# HomeLight.net
KiCad netlist of a schematic drawn in Altium Designer
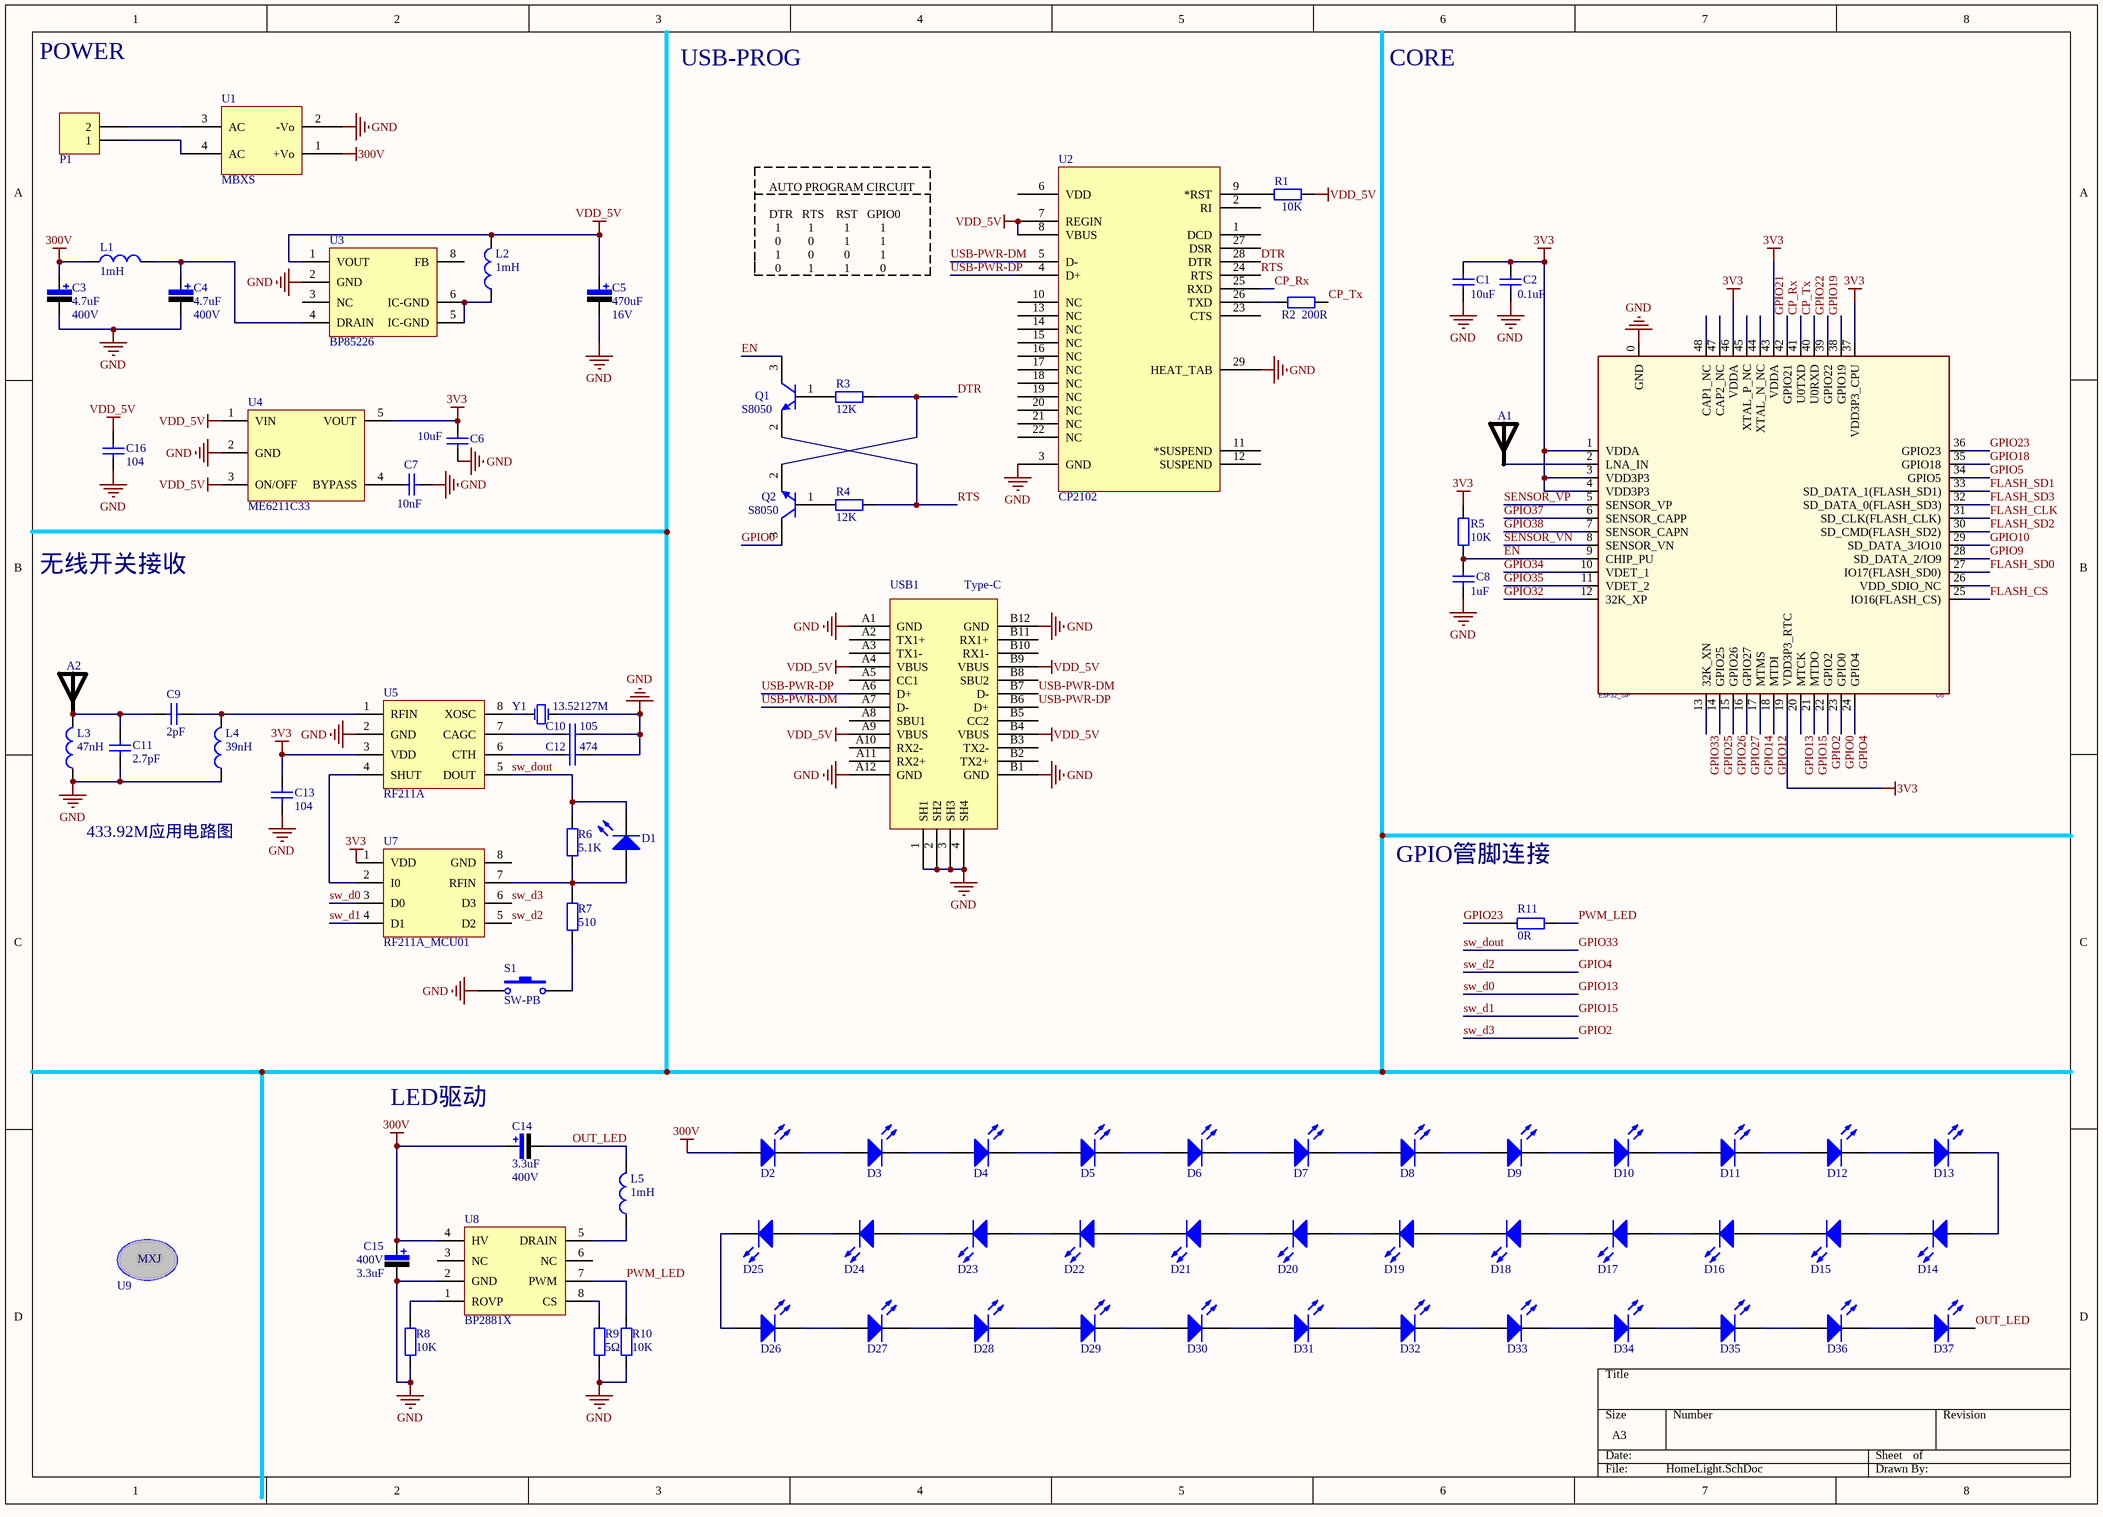
[diagram p0: HomeLight.SchDoc]

(export (version "E")
  (design (tool "Eeschema 10.0.6"))
  (components
    (comp (ref "A1")
      (value "ANT")
      (footprint "ANT5020R2400")
      (libsource (lib "PCBSchlib_SEU_RobotLab") (part "ANT"))
    )
    (comp (ref "A2")
      (value "ANT")
      (footprint "PCBPcblib_SEU_RobotLab:ANT15030R433")
      (libsource (lib "PCBSchlib_SEU_RobotLab") (part "ANT"))
    )
    (comp (ref "C1")
      (value "10uF")
      (footprint "0603-2")
      (description "无极性电容")
      (fields (field (name "PUBLISHER") "Altium Limited"))
      (libsource (lib "PCBSchlib_SEU_RobotLab") (part "Cap"))
    )
    (comp (ref "C2")
      (value "0.1uF")
      (footprint "0603-2")
      (description "无极性电容")
      (fields (field (name "PUBLISHER") "Altium Limited"))
      (libsource (lib "PCBSchlib_SEU_RobotLab") (part "Cap"))
    )
    (comp (ref "C3")
      (value "4.7uF")
      (footprint "SMD-EC-F8")
      (description "极性电解电容")
      (fields
        (field (name "VOL") "400V")
        (field (name "Comment") "Cap Pol")
        (field (name "PUBLISHER") "Altium Limited")
      )
      (libsource (lib "PCBSchlib_SEU_RobotLab") (part "Cap Pol"))
    )
    (comp (ref "C4")
      (value "4.7uF")
      (footprint "SMD-EC-F8")
      (description "极性电解电容")
      (fields
        (field (name "VOL") "400V")
        (field (name "Comment") "Cap Pol")
        (field (name "PUBLISHER") "Altium Limited")
      )
      (libsource (lib "PCBSchlib_SEU_RobotLab") (part "Cap Pol"))
    )
    (comp (ref "C5")
      (value "470uF")
      (footprint "SMD-EC-F6")
      (description "极性电解电容")
      (fields
        (field (name "VOL") "16V")
        (field (name "Comment") "Cap Pol")
        (field (name "PUBLISHER") "Altium Limited")
      )
      (libsource (lib "PCBSchlib_SEU_RobotLab") (part "Cap Pol"))
    )
    (comp (ref "C6")
      (value "10uF")
      (footprint "0603-2")
      (description "无极性电容")
      (fields (field (name "PUBLISHER") "Altium Limited"))
      (libsource (lib "PCBSchlib_SEU_RobotLab") (part "Cap"))
    )
    (comp (ref "C7")
      (value "10nF")
      (footprint "0603-2")
      (description "无极性电容")
      (fields (field (name "PUBLISHER") "Altium Limited"))
      (libsource (lib "PCBSchlib_SEU_RobotLab") (part "Cap"))
    )
    (comp (ref "C8")
      (value "1uF")
      (footprint "0603-2")
      (description "无极性电容")
      (fields (field (name "PUBLISHER") "Altium Limited"))
      (libsource (lib "PCBSchlib_SEU_RobotLab") (part "Cap"))
    )
    (comp (ref "C9")
      (value "2pF")
      (footprint "0603-2")
      (description "无极性电容")
      (fields (field (name "Comment") "Cap") (field (name "PUBLISHER") "Altium Limited"))
      (libsource (lib "PCBSchlib_SEU_RobotLab") (part "Cap"))
    )
    (comp (ref "C10")
      (value "105")
      (footprint "0603-2")
      (description "无极性电容")
      (fields (field (name "Comment") "Cap") (field (name "PUBLISHER") "Altium Limited"))
      (libsource (lib "PCBSchlib_SEU_RobotLab") (part "Cap"))
    )
    (comp (ref "C11")
      (value "2.7pF")
      (footprint "0603-2")
      (description "无极性电容")
      (fields (field (name "Comment") "Cap") (field (name "PUBLISHER") "Altium Limited"))
      (libsource (lib "PCBSchlib_SEU_RobotLab") (part "Cap"))
    )
    (comp (ref "C12")
      (value "474")
      (footprint "0603-2")
      (description "无极性电容")
      (fields (field (name "Comment") "Cap") (field (name "PUBLISHER") "Altium Limited"))
      (libsource (lib "PCBSchlib_SEU_RobotLab") (part "Cap"))
    )
    (comp (ref "C13")
      (value "104")
      (footprint "0603-2")
      (description "无极性电容")
      (fields (field (name "Comment") "Cap") (field (name "PUBLISHER") "Altium Limited"))
      (libsource (lib "PCBSchlib_SEU_RobotLab") (part "Cap"))
    )
    (comp (ref "C14")
      (value "3.3uF")
      (footprint "SMD-EC-F8")
      (description "极性电解电容")
      (fields
        (field (name "VOL") "400V")
        (field (name "Comment") "Cap Pol")
        (field (name "PUBLISHER") "Altium Limited")
      )
      (libsource (lib "") (part "Cap Pol_1"))
    )
    (comp (ref "C15")
      (value "3.3uF")
      (footprint "SMD-EC-F8")
      (description "极性电解电容")
      (fields
        (field (name "VOL") "400V")
        (field (name "Comment") "Cap Pol")
        (field (name "PUBLISHER") "Altium Limited")
      )
      (libsource (lib "PCBSchlib_SEU_RobotLab") (part "Cap Pol"))
    )
    (comp (ref "C16")
      (value "104")
      (footprint "0603-2")
      (description "无极性电容")
      (fields (field (name "Comment") "Cap") (field (name "PUBLISHER") "Altium Limited"))
      (libsource (lib "PCBSchlib_SEU_RobotLab") (part "Cap"))
    )
    (comp (ref "D1")
      (value "LED0")
      (footprint "LED_0603")
      (description "发光二极管")
      (fields (field (name "PUBLISHER") "Altium Limited"))
      (libsource (lib "PCBSchlib_SEU_RobotLab") (part "LED0"))
    )
    (comp (ref "D2")
      (value "LED0")
      (footprint "LED-3528")
      (description "发光二极管")
      (fields (field (name "PUBLISHER") "Altium Limited"))
      (libsource (lib "PCBSchlib_SEU_RobotLab") (part "LED0"))
    )
    (comp (ref "D3")
      (value "LED0")
      (footprint "LED-3528")
      (description "发光二极管")
      (fields (field (name "PUBLISHER") "Altium Limited"))
      (libsource (lib "PCBSchlib_SEU_RobotLab") (part "LED0"))
    )
    (comp (ref "D4")
      (value "LED0")
      (footprint "LED-3528")
      (description "发光二极管")
      (fields (field (name "PUBLISHER") "Altium Limited"))
      (libsource (lib "PCBSchlib_SEU_RobotLab") (part "LED0"))
    )
    (comp (ref "D5")
      (value "LED0")
      (footprint "LED-3528")
      (description "发光二极管")
      (fields (field (name "PUBLISHER") "Altium Limited"))
      (libsource (lib "PCBSchlib_SEU_RobotLab") (part "LED0"))
    )
    (comp (ref "D6")
      (value "LED0")
      (footprint "LED-3528")
      (description "发光二极管")
      (fields (field (name "PUBLISHER") "Altium Limited"))
      (libsource (lib "PCBSchlib_SEU_RobotLab") (part "LED0"))
    )
    (comp (ref "D7")
      (value "LED0")
      (footprint "LED-3528")
      (description "发光二极管")
      (fields (field (name "PUBLISHER") "Altium Limited"))
      (libsource (lib "PCBSchlib_SEU_RobotLab") (part "LED0"))
    )
    (comp (ref "D8")
      (value "LED0")
      (footprint "LED-3528")
      (description "发光二极管")
      (fields (field (name "PUBLISHER") "Altium Limited"))
      (libsource (lib "PCBSchlib_SEU_RobotLab") (part "LED0"))
    )
    (comp (ref "D9")
      (value "LED0")
      (footprint "LED-3528")
      (description "发光二极管")
      (fields (field (name "PUBLISHER") "Altium Limited"))
      (libsource (lib "PCBSchlib_SEU_RobotLab") (part "LED0"))
    )
    (comp (ref "D10")
      (value "LED0")
      (footprint "LED-3528")
      (description "发光二极管")
      (fields (field (name "PUBLISHER") "Altium Limited"))
      (libsource (lib "PCBSchlib_SEU_RobotLab") (part "LED0"))
    )
    (comp (ref "D11")
      (value "LED0")
      (footprint "LED-3528")
      (description "发光二极管")
      (fields (field (name "PUBLISHER") "Altium Limited"))
      (libsource (lib "PCBSchlib_SEU_RobotLab") (part "LED0"))
    )
    (comp (ref "D12")
      (value "LED0")
      (footprint "LED-3528")
      (description "发光二极管")
      (fields (field (name "PUBLISHER") "Altium Limited"))
      (libsource (lib "PCBSchlib_SEU_RobotLab") (part "LED0"))
    )
    (comp (ref "D13")
      (value "LED0")
      (footprint "LED-3528")
      (description "发光二极管")
      (fields (field (name "PUBLISHER") "Altium Limited"))
      (libsource (lib "PCBSchlib_SEU_RobotLab") (part "LED0"))
    )
    (comp (ref "D14")
      (value "LED0")
      (footprint "LED-3528")
      (description "发光二极管")
      (fields (field (name "PUBLISHER") "Altium Limited"))
      (libsource (lib "PCBSchlib_SEU_RobotLab") (part "LED0"))
    )
    (comp (ref "D15")
      (value "LED0")
      (footprint "LED-3528")
      (description "发光二极管")
      (fields (field (name "PUBLISHER") "Altium Limited"))
      (libsource (lib "PCBSchlib_SEU_RobotLab") (part "LED0"))
    )
    (comp (ref "D16")
      (value "LED0")
      (footprint "LED-3528")
      (description "发光二极管")
      (fields (field (name "PUBLISHER") "Altium Limited"))
      (libsource (lib "PCBSchlib_SEU_RobotLab") (part "LED0"))
    )
    (comp (ref "D17")
      (value "LED0")
      (footprint "LED-3528")
      (description "发光二极管")
      (fields (field (name "PUBLISHER") "Altium Limited"))
      (libsource (lib "PCBSchlib_SEU_RobotLab") (part "LED0"))
    )
    (comp (ref "D18")
      (value "LED0")
      (footprint "LED-3528")
      (description "发光二极管")
      (fields (field (name "PUBLISHER") "Altium Limited"))
      (libsource (lib "PCBSchlib_SEU_RobotLab") (part "LED0"))
    )
    (comp (ref "D19")
      (value "LED0")
      (footprint "LED-3528")
      (description "发光二极管")
      (fields (field (name "PUBLISHER") "Altium Limited"))
      (libsource (lib "PCBSchlib_SEU_RobotLab") (part "LED0"))
    )
    (comp (ref "D20")
      (value "LED0")
      (footprint "LED-3528")
      (description "发光二极管")
      (fields (field (name "PUBLISHER") "Altium Limited"))
      (libsource (lib "PCBSchlib_SEU_RobotLab") (part "LED0"))
    )
    (comp (ref "D21")
      (value "LED0")
      (footprint "LED-3528")
      (description "发光二极管")
      (fields (field (name "PUBLISHER") "Altium Limited"))
      (libsource (lib "PCBSchlib_SEU_RobotLab") (part "LED0"))
    )
    (comp (ref "D22")
      (value "LED0")
      (footprint "LED-3528")
      (description "发光二极管")
      (fields (field (name "PUBLISHER") "Altium Limited"))
      (libsource (lib "PCBSchlib_SEU_RobotLab") (part "LED0"))
    )
    (comp (ref "D23")
      (value "LED0")
      (footprint "LED-3528")
      (description "发光二极管")
      (fields (field (name "PUBLISHER") "Altium Limited"))
      (libsource (lib "PCBSchlib_SEU_RobotLab") (part "LED0"))
    )
    (comp (ref "D24")
      (value "LED0")
      (footprint "LED-3528")
      (description "发光二极管")
      (fields (field (name "PUBLISHER") "Altium Limited"))
      (libsource (lib "PCBSchlib_SEU_RobotLab") (part "LED0"))
    )
    (comp (ref "D25")
      (value "LED0")
      (footprint "LED-3528")
      (description "发光二极管")
      (fields (field (name "PUBLISHER") "Altium Limited"))
      (libsource (lib "PCBSchlib_SEU_RobotLab") (part "LED0"))
    )
    (comp (ref "D26")
      (value "LED0")
      (footprint "LED-3528")
      (description "发光二极管")
      (fields (field (name "PUBLISHER") "Altium Limited"))
      (libsource (lib "PCBSchlib_SEU_RobotLab") (part "LED0"))
    )
    (comp (ref "D27")
      (value "LED0")
      (footprint "LED-3528")
      (description "发光二极管")
      (fields (field (name "PUBLISHER") "Altium Limited"))
      (libsource (lib "PCBSchlib_SEU_RobotLab") (part "LED0"))
    )
    (comp (ref "D28")
      (value "LED0")
      (footprint "LED-3528")
      (description "发光二极管")
      (fields (field (name "PUBLISHER") "Altium Limited"))
      (libsource (lib "PCBSchlib_SEU_RobotLab") (part "LED0"))
    )
    (comp (ref "D29")
      (value "LED0")
      (footprint "LED-3528")
      (description "发光二极管")
      (fields (field (name "PUBLISHER") "Altium Limited"))
      (libsource (lib "PCBSchlib_SEU_RobotLab") (part "LED0"))
    )
    (comp (ref "D30")
      (value "LED0")
      (footprint "LED-3528")
      (description "发光二极管")
      (fields (field (name "PUBLISHER") "Altium Limited"))
      (libsource (lib "PCBSchlib_SEU_RobotLab") (part "LED0"))
    )
    (comp (ref "D31")
      (value "LED0")
      (footprint "LED-3528")
      (description "发光二极管")
      (fields (field (name "PUBLISHER") "Altium Limited"))
      (libsource (lib "PCBSchlib_SEU_RobotLab") (part "LED0"))
    )
    (comp (ref "D32")
      (value "LED0")
      (footprint "LED-3528")
      (description "发光二极管")
      (fields (field (name "PUBLISHER") "Altium Limited"))
      (libsource (lib "PCBSchlib_SEU_RobotLab") (part "LED0"))
    )
    (comp (ref "D33")
      (value "LED0")
      (footprint "LED-3528")
      (description "发光二极管")
      (fields (field (name "PUBLISHER") "Altium Limited"))
      (libsource (lib "PCBSchlib_SEU_RobotLab") (part "LED0"))
    )
    (comp (ref "D34")
      (value "LED0")
      (footprint "LED-3528")
      (description "发光二极管")
      (fields (field (name "PUBLISHER") "Altium Limited"))
      (libsource (lib "PCBSchlib_SEU_RobotLab") (part "LED0"))
    )
    (comp (ref "D35")
      (value "LED0")
      (footprint "LED-3528")
      (description "发光二极管")
      (fields (field (name "PUBLISHER") "Altium Limited"))
      (libsource (lib "PCBSchlib_SEU_RobotLab") (part "LED0"))
    )
    (comp (ref "D36")
      (value "LED0")
      (footprint "LED-3528")
      (description "发光二极管")
      (fields (field (name "PUBLISHER") "Altium Limited"))
      (libsource (lib "PCBSchlib_SEU_RobotLab") (part "LED0"))
    )
    (comp (ref "D37")
      (value "LED0")
      (footprint "LED-3528")
      (description "发光二极管")
      (fields (field (name "PUBLISHER") "Altium Limited"))
      (libsource (lib "PCBSchlib_SEU_RobotLab") (part "LED0"))
    )
    (comp (ref "L1")
      (value "1mH")
      (footprint "L12x12")
      (description "电感")
      (fields (field (name "Comment") "Inductor") (field (name "PUBLISHER") "Altium Limited"))
      (libsource (lib "PCBSchlib_SEU_RobotLab") (part "Inductor"))
    )
    (comp (ref "L2")
      (value "1mH")
      (footprint "L12x12")
      (description "电感")
      (fields (field (name "Comment") "Inductor") (field (name "PUBLISHER") "Altium Limited"))
      (libsource (lib "PCBSchlib_SEU_RobotLab") (part "Inductor"))
    )
    (comp (ref "L3")
      (value "47nH")
      (footprint "PCBPcblib_SEU_RobotLab:0603-1")
      (description "电感")
      (fields (field (name "Comment") "Inductor") (field (name "PUBLISHER") "Altium Limited"))
      (libsource (lib "PCBSchlib_SEU_RobotLab") (part "Inductor"))
    )
    (comp (ref "L4")
      (value "39nH")
      (footprint "PCBPcblib_SEU_RobotLab:0603-1")
      (description "电感")
      (fields (field (name "Comment") "Inductor") (field (name "PUBLISHER") "Altium Limited"))
      (libsource (lib "PCBSchlib_SEU_RobotLab") (part "Inductor"))
    )
    (comp (ref "L5")
      (value "1mH")
      (footprint "L12x12")
      (description "电感")
      (fields (field (name "Comment") "Inductor") (field (name "PUBLISHER") "Altium Limited"))
      (libsource (lib "PCBSchlib_SEU_RobotLab") (part "Inductor"))
    )
    (comp (ref "P1")
      (value "Header 2")
      (footprint "PCBPcblib_SEU_RobotLab:HDR2X1_焊接版")
      (description "接插件")
      (fields (field (name "PUBLISHER") "Altium Limited"))
      (libsource (lib "PCBSchlib_SEU_RobotLab") (part "Header 2"))
    )
    (comp (ref "Q1")
      (value "S8050")
      (footprint "PCBPcblib_SEU_RobotLab:SOT-23")
      (description "NPN三极管")
      (fields (field (name "PUBLISHER") "Altium Limited"))
      (libsource (lib "PCBSchlib_SEU_RobotLab") (part "Triode-NPN"))
    )
    (comp (ref "Q2")
      (value "S8050")
      (footprint "PCBPcblib_SEU_RobotLab:SOT-23")
      (description "NPN三极管")
      (fields (field (name "PUBLISHER") "Altium Limited"))
      (libsource (lib "PCBSchlib_SEU_RobotLab") (part "Triode-NPN"))
    )
    (comp (ref "R1")
      (value "10K")
      (footprint "0603-1")
      (description "贴片电阻")
      (fields (field (name "PUBLISHER") "Altium Limited"))
      (libsource (lib "PCBSchlib_SEU_RobotLab") (part "Res1"))
    )
    (comp (ref "R2")
      (value "200R")
      (footprint "0603-1")
      (description "贴片电阻")
      (fields (field (name "PUBLISHER") "Altium Limited"))
      (libsource (lib "PCBSchlib_SEU_RobotLab") (part "Res1"))
    )
    (comp (ref "R3")
      (value "12K")
      (footprint "0603-1")
      (description "贴片电阻")
      (fields (field (name "PUBLISHER") "Altium Limited"))
      (libsource (lib "PCBSchlib_SEU_RobotLab") (part "Res1"))
    )
    (comp (ref "R4")
      (value "12K")
      (footprint "0603-1")
      (description "贴片电阻")
      (fields (field (name "PUBLISHER") "Altium Limited"))
      (libsource (lib "PCBSchlib_SEU_RobotLab") (part "Res1"))
    )
    (comp (ref "R5")
      (value "10K")
      (footprint "0603-1")
      (description "贴片电阻")
      (fields (field (name "PUBLISHER") "Altium Limited"))
      (libsource (lib "") (part "Res1_2"))
    )
    (comp (ref "R6")
      (value "5.1K")
      (footprint "0603-1")
      (description "贴片电阻")
      (fields (field (name "Comment") "Res1") (field (name "PUBLISHER") "Altium Limited"))
      (libsource (lib "") (part "Res1_1"))
    )
    (comp (ref "R7")
      (value "510")
      (footprint "0603-1")
      (description "贴片电阻")
      (fields (field (name "Comment") "Res1") (field (name "PUBLISHER") "Altium Limited"))
      (libsource (lib "") (part "Res1_1"))
    )
    (comp (ref "R8")
      (value "10K")
      (footprint "0603-1")
      (description "贴片电阻")
      (fields (field (name "Comment") "Res1") (field (name "PUBLISHER") "Altium Limited"))
      (libsource (lib "") (part "Res1_1"))
    )
    (comp (ref "R9")
      (value "5Ω")
      (footprint "0603-1")
      (description "贴片电阻")
      (fields (field (name "Comment") "Res1") (field (name "PUBLISHER") "Altium Limited"))
      (libsource (lib "") (part "Res1_1"))
    )
    (comp (ref "R10")
      (value "10K")
      (footprint "0603-1")
      (description "贴片电阻")
      (fields (field (name "Comment") "Res1") (field (name "PUBLISHER") "Altium Limited"))
      (libsource (lib "") (part "Res1_1"))
    )
    (comp (ref "R11")
      (value "0R")
      (footprint "0603-1")
      (description "贴片电阻")
      (fields (field (name "Comment") "Res1") (field (name "PUBLISHER") "Altium Limited"))
      (libsource (lib "PCBSchlib_SEU_RobotLab") (part "Res1"))
    )
    (comp (ref "S1")
      (value "SW-PB")
      (footprint "SW_PB2_A1")
      (description "微动开关")
      (fields (field (name "PUBLISHER") "Altium Limited"))
      (libsource (lib "PCBSchlib_SEU_RobotLab") (part "SW-PB"))
    )
    (comp (ref "U1")
      (value "MBXS")
      (footprint "PCBPcblib_SEU_RobotLab:MBXS")
      (description "整流桥")
      (libsource (lib "PCBSchlib_SEU_RobotLab") (part "MBXS"))
    )
    (comp (ref "U2")
      (value "CP2102")
      (footprint "QFN-28")
      (description "USB转TTL")
      (libsource (lib "mLib") (part "CP2102"))
    )
    (comp (ref "U3")
      (value "BP85226")
      (footprint "PCBPcblib_SEU_RobotLab:BP85226-BP2881")
      (description "开关电源驱动芯片")
      (libsource (lib "PCBSchlib_SEU_RobotLab") (part "BP85226"))
    )
    (comp (ref "U4")
      (value "ME6211C33")
      (footprint "SOT23-5")
      (description "LDO")
      (libsource (lib "PCBSchlib_SEU_RobotLab") (part "LP2992"))
    )
    (comp (ref "U5")
      (value "RF211A")
      (footprint "PCBPcblib_SEU_RobotLab:SOIC-8")
      (description "315M无线接收芯片")
      (libsource (lib "PCBSchlib_SEU_RobotLab") (part "RF211A"))
    )
    (comp (ref "U6")
      (value "ESP32_SIP")
      (footprint "QFN-48_7X7")
      (libsource (lib "PCBSchlib_SEU_RobotLab") (part "ESP32-PICO"))
    )
    (comp (ref "U7")
      (value "RF211A_MCU01")
      (footprint "PCBPcblib_SEU_RobotLab:SOIC-8")
      (description "无线接收芯片的解码芯片")
      (libsource (lib "PCBSchlib_SEU_RobotLab") (part "RF211A_MCU01"))
    )
    (comp (ref "U8")
      (value "BP2881X")
      (footprint "PCBPcblib_SEU_RobotLab:BP85226-BP2881")
      (description "PWM调光非隔离降压型LED恒流驱动芯片")
      (libsource (lib "PCBSchlib_SEU_RobotLab") (part "BP2881X"))
    )
    (comp (ref "U9")
      (value "logo_MXJ")
      (footprint "PCBPcblib_SEU_RobotLab:logo_MXJ")
      (libsource (lib "PCBSchlib_SEU_RobotLab") (part "logo_MXJ"))
    )
    (comp (ref "USB1")
      (value "Type-C")
      (footprint "Type-C-TOP")
      (libsource (lib "PCBSchlib_SEU_RobotLab") (part "USB-Type-C-TOP"))
    )
    (comp (ref "Y1")
      (value "13.52127M")
      (footprint "X-SM49")
      (description "晶振")
      (fields (field (name "Comment") "XTAL") (field (name "PUBLISHER") "Altium Limited"))
      (libsource (lib "PCBSchlib_SEU_RobotLab") (part "XTAL"))
    )
  )
  (nets
    (net (code "1") (name "/CP_Rx") (class "Default")
      (node (ref "U2") (pin "25") (pinfunction "RXD_25") (pintype "passive"))
      (node (ref "U6") (pin "41") (pinfunction "U0TXD_41") (pintype "power_in"))
    )
    (net (code "2") (name "/CP_Tx") (class "Default")
      (node (ref "R2") (pin "1") (pinfunction "1_1") (pintype "passive"))
      (node (ref "U6") (pin "40") (pinfunction "U0RXD_40") (pintype "power_in"))
    )
    (net (code "3") (name "/DTR") (class "Default")
      (node (ref "Q2") (pin "2") (pinfunction "E_2") (pintype "passive"))
      (node (ref "R3") (pin "1") (pinfunction "1_1") (pintype "passive"))
      (node (ref "U2") (pin "28") (pinfunction "DTR_28") (pintype "passive"))
    )
    (net (code "4") (name "/EN") (class "Default")
      (node (ref "C8") (pin "1") (pinfunction "1_1") (pintype "passive"))
      (node (ref "Q1") (pin "3") (pinfunction "C_3") (pintype "passive"))
      (node (ref "R5") (pin "2") (pinfunction "2_2") (pintype "passive"))
      (node (ref "U6") (pin "9") (pinfunction "CHIP_PU_9") (pintype "passive"))
    )
    (net (code "5") (name "/FLASH_CLK") (class "Default")
      (node (ref "U6") (pin "31") (pinfunction "SD_CLK(FLASH_CLK)_31") (pintype "passive"))
    )
    (net (code "6") (name "/FLASH_CS") (class "Default")
      (node (ref "U6") (pin "25") (pinfunction "IO16(FLASH_CS)_25") (pintype "passive"))
    )
    (net (code "7") (name "/FLASH_SD0") (class "Default")
      (node (ref "U6") (pin "27") (pinfunction "IO17(FLASH_SD0)_27") (pintype "passive"))
    )
    (net (code "8") (name "/FLASH_SD1") (class "Default")
      (node (ref "U6") (pin "33") (pinfunction "SD_DATA_1(FLASH_SD1)_33") (pintype "passive"))
    )
    (net (code "9") (name "/FLASH_SD2") (class "Default")
      (node (ref "U6") (pin "30") (pinfunction "SD_CMD(FLASH_SD2)_30") (pintype "passive"))
    )
    (net (code "10") (name "/FLASH_SD3") (class "Default")
      (node (ref "U6") (pin "32") (pinfunction "SD_DATA_0(FLASH_SD3)_32") (pintype "passive"))
    )
    (net (code "11") (name "/GPIO0") (class "Default")
      (node (ref "Q2") (pin "3") (pinfunction "C_3") (pintype "passive"))
      (node (ref "U6") (pin "23") (pinfunction "GPIO0_23") (pintype "passive"))
    )
    (net (code "12") (name "/GPIO2") (class "Default")
      (node (ref "U6") (pin "22") (pinfunction "GPIO2_22") (pintype "passive"))
      (node (ref "U7") (pin "6") (pinfunction "D3_6") (pintype "passive"))
    )
    (net (code "13") (name "/GPIO4") (class "Default")
      (node (ref "U6") (pin "24") (pinfunction "GPIO4_24") (pintype "passive"))
      (node (ref "U7") (pin "5") (pinfunction "D2_5") (pintype "passive"))
    )
    (net (code "14") (name "/GPIO5") (class "Default")
      (node (ref "U6") (pin "34") (pinfunction "GPIO5_34") (pintype "passive"))
    )
    (net (code "15") (name "/GPIO9") (class "Default")
      (node (ref "U6") (pin "28") (pinfunction "SD_DATA_2/IO9_28") (pintype "passive"))
    )
    (net (code "16") (name "/GPIO10") (class "Default")
      (node (ref "U6") (pin "29") (pinfunction "SD_DATA_3/IO10_29") (pintype "passive"))
    )
    (net (code "17") (name "/GPIO12") (class "Default")
      (node (ref "U6") (pin "18") (pinfunction "MTDI_18") (pintype "passive"))
    )
    (net (code "18") (name "/GPIO13") (class "Default")
      (node (ref "U6") (pin "20") (pinfunction "MTCK_20") (pintype "passive"))
      (node (ref "U7") (pin "3") (pinfunction "D0_3") (pintype "passive"))
    )
    (net (code "19") (name "/GPIO14") (class "Default")
      (node (ref "U6") (pin "17") (pinfunction "MTMS_17") (pintype "passive"))
    )
    (net (code "20") (name "/GPIO15") (class "Default")
      (node (ref "U6") (pin "21") (pinfunction "MTDO_21") (pintype "passive"))
      (node (ref "U7") (pin "4") (pinfunction "D1_4") (pintype "passive"))
    )
    (net (code "21") (name "/GPIO18") (class "Default")
      (node (ref "U6") (pin "35") (pinfunction "GPIO18_35") (pintype "passive"))
    )
    (net (code "22") (name "/GPIO19") (class "Default")
      (node (ref "U6") (pin "38") (pinfunction "GPIO19_38") (pintype "passive"))
    )
    (net (code "23") (name "/GPIO21") (class "Default")
      (node (ref "U6") (pin "42") (pinfunction "GPIO21_42") (pintype "passive"))
    )
    (net (code "24") (name "/GPIO22") (class "Default")
      (node (ref "U6") (pin "39") (pinfunction "GPIO22_39") (pintype "passive"))
    )
    (net (code "25") (name "/GPIO23") (class "Default")
      (node (ref "R11") (pin "2") (pinfunction "2_2") (pintype "passive"))
      (node (ref "U6") (pin "36") (pinfunction "GPIO23_36") (pintype "passive"))
    )
    (net (code "26") (name "/GPIO25") (class "Default")
      (node (ref "U6") (pin "14") (pinfunction "GPIO25_14") (pintype "passive"))
    )
    (net (code "27") (name "/GPIO26") (class "Default")
      (node (ref "U6") (pin "15") (pinfunction "GPIO26_15") (pintype "passive"))
    )
    (net (code "28") (name "/GPIO27") (class "Default")
      (node (ref "U6") (pin "16") (pinfunction "GPIO27_16") (pintype "passive"))
    )
    (net (code "29") (name "/GPIO32") (class "Default")
      (node (ref "U6") (pin "12") (pinfunction "32K_XP_12") (pintype "passive"))
    )
    (net (code "30") (name "/GPIO33") (class "Default")
      (node (ref "D1") (pin "2") (pinfunction "K_2") (pintype "passive"))
      (node (ref "R6") (pin "2") (pinfunction "2_2") (pintype "passive"))
      (node (ref "U5") (pin "5") (pinfunction "DOUT_5") (pintype "passive"))
      (node (ref "U6") (pin "13") (pinfunction "32K_XN_13") (pintype "passive"))
    )
    (net (code "31") (name "/GPIO34") (class "Default")
      (node (ref "U6") (pin "10") (pinfunction "VDET_1_10") (pintype "passive"))
    )
    (net (code "32") (name "/GPIO35") (class "Default")
      (node (ref "U6") (pin "11") (pinfunction "VDET_2_11") (pintype "passive"))
    )
    (net (code "33") (name "/GPIO37") (class "Default")
      (node (ref "U6") (pin "6") (pinfunction "SENSOR_CAPP_6") (pintype "passive"))
    )
    (net (code "34") (name "/GPIO38") (class "Default")
      (node (ref "U6") (pin "7") (pinfunction "SENSOR_CAPN_7") (pintype "passive"))
    )
    (net (code "35") (name "/OUT_LED") (class "Default")
      (node (ref "C14") (pin "2") (pinfunction "2_2") (pintype "passive"))
      (node (ref "D37") (pin "2") (pinfunction "K_2") (pintype "passive"))
      (node (ref "L5") (pin "2") (pinfunction "2_2") (pintype "passive"))
    )
    (net (code "36") (name "/PWM_LED") (class "Default")
      (node (ref "R10") (pin "2") (pinfunction "2_2") (pintype "passive"))
      (node (ref "R11") (pin "1") (pinfunction "1_1") (pintype "passive"))
      (node (ref "U8") (pin "7") (pinfunction "PWM_7") (pintype "passive"))
    )
    (net (code "37") (name "/RTS") (class "Default")
      (node (ref "Q1") (pin "2") (pinfunction "E_2") (pintype "passive"))
      (node (ref "R4") (pin "1") (pinfunction "1_1") (pintype "passive"))
      (node (ref "U2") (pin "24") (pinfunction "RTS_24") (pintype "passive"))
    )
    (net (code "38") (name "/SENSOR_VN") (class "Default")
      (node (ref "U6") (pin "8") (pinfunction "SENSOR_VN_8") (pintype "passive"))
    )
    (net (code "39") (name "/SENSOR_VP") (class "Default")
      (node (ref "U6") (pin "5") (pinfunction "SENSOR_VP_5") (pintype "passive"))
    )
    (net (code "40") (name "/USB-PWR-DM") (class "Default")
      (node (ref "U2") (pin "5") (pinfunction "D-_5") (pintype "passive"))
      (node (ref "USB1") (pin "A7") (pinfunction "D-_A7") (pintype "passive"))
      (node (ref "USB1") (pin "B7") (pinfunction "D-_B7") (pintype "passive"))
    )
    (net (code "41") (name "/USB-PWR-DP") (class "Default")
      (node (ref "U2") (pin "4") (pinfunction "D+_4") (pintype "passive"))
      (node (ref "USB1") (pin "A6") (pinfunction "D+_A6") (pintype "passive"))
      (node (ref "USB1") (pin "B6") (pinfunction "D+_B6") (pintype "passive"))
    )
    (net (code "42") (name "3V3") (class "Default")
      (node (ref "C1") (pin "2") (pinfunction "2_2") (pintype "passive"))
      (node (ref "C13") (pin "1") (pinfunction "1_1") (pintype "passive"))
      (node (ref "C2") (pin "2") (pinfunction "2_2") (pintype "passive"))
      (node (ref "C6") (pin "2") (pinfunction "2_2") (pintype "passive"))
      (node (ref "R5") (pin "1") (pinfunction "1_1") (pintype "passive"))
      (node (ref "U4") (pin "5") (pinfunction "VOUT_5") (pintype "passive"))
      (node (ref "U5") (pin "3") (pinfunction "VDD_3") (pintype "passive"))
      (node (ref "U6") (pin "1") (pinfunction "VDDA_1") (pintype "power_in"))
      (node (ref "U6") (pin "19") (pinfunction "VDD3P3_RTC_19") (pintype "power_in"))
      (node (ref "U6") (pin "3") (pinfunction "VDD3P3_3") (pintype "power_in"))
      (node (ref "U6") (pin "37") (pinfunction "VDD3P3_CPU_37") (pintype "power_in"))
      (node (ref "U6") (pin "4") (pinfunction "VDD3P3_4") (pintype "power_in"))
      (node (ref "U6") (pin "43") (pinfunction "VDDA_43") (pintype "power_in"))
      (node (ref "U6") (pin "46") (pinfunction "VDDA_46") (pintype "power_in"))
      (node (ref "U7") (pin "1") (pinfunction "VDD_1") (pintype "passive"))
    )
    (net (code "43") (name "300V") (class "Default")
      (node (ref "C14") (pin "1") (pinfunction "1_1") (pintype "passive"))
      (node (ref "C15") (pin "1") (pinfunction "1_1") (pintype "passive"))
      (node (ref "C3") (pin "1") (pinfunction "1_1") (pintype "passive"))
      (node (ref "D2") (pin "1") (pinfunction "A_1") (pintype "passive"))
      (node (ref "L1") (pin "1") (pinfunction "1_1") (pintype "passive"))
      (node (ref "U1") (pin "1") (pinfunction "+Vo_1") (pintype "passive"))
      (node (ref "U8") (pin "4") (pinfunction "HV_4") (pintype "passive"))
    )
    (net (code "44") (name "GND") (class "Default")
      (node (ref "C1") (pin "1") (pinfunction "1_1") (pintype "passive"))
      (node (ref "C10") (pin "1") (pinfunction "1_1") (pintype "passive"))
      (node (ref "C11") (pin "2") (pinfunction "2_2") (pintype "passive"))
      (node (ref "C12") (pin "1") (pinfunction "1_1") (pintype "passive"))
      (node (ref "C13") (pin "2") (pinfunction "2_2") (pintype "passive"))
      (node (ref "C15") (pin "2") (pinfunction "2_2") (pintype "passive"))
      (node (ref "C16") (pin "2") (pinfunction "2_2") (pintype "passive"))
      (node (ref "C2") (pin "1") (pinfunction "1_1") (pintype "passive"))
      (node (ref "C3") (pin "2") (pinfunction "2_2") (pintype "passive"))
      (node (ref "C4") (pin "2") (pinfunction "2_2") (pintype "passive"))
      (node (ref "C5") (pin "2") (pinfunction "2_2") (pintype "passive"))
      (node (ref "C6") (pin "1") (pinfunction "1_1") (pintype "passive"))
      (node (ref "C7") (pin "1") (pinfunction "1_1") (pintype "passive"))
      (node (ref "C8") (pin "2") (pinfunction "2_2") (pintype "passive"))
      (node (ref "L3") (pin "1") (pinfunction "1_1") (pintype "passive"))
      (node (ref "L4") (pin "1") (pinfunction "1_1") (pintype "passive"))
      (node (ref "R10") (pin "1") (pinfunction "1_1") (pintype "passive"))
      (node (ref "R8") (pin "1") (pinfunction "1_1") (pintype "passive"))
      (node (ref "R9") (pin "1") (pinfunction "1_1") (pintype "passive"))
      (node (ref "S1") (pin "1") (pinfunction "1_1") (pintype "passive"))
      (node (ref "U1") (pin "2") (pinfunction "-Vo_2") (pintype "passive"))
      (node (ref "U2") (pin "29") (pinfunction "HEAT_TAB_29") (pintype "passive"))
      (node (ref "U2") (pin "3") (pinfunction "GND_3") (pintype "passive"))
      (node (ref "U3") (pin "2") (pinfunction "GND_2") (pintype "passive"))
      (node (ref "U4") (pin "2") (pinfunction "GND_2") (pintype "passive"))
      (node (ref "U5") (pin "2") (pinfunction "GND_2") (pintype "passive"))
      (node (ref "U6") (pin "0") (pinfunction "GND_0") (pintype "power_in"))
      (node (ref "U8") (pin "2") (pinfunction "GND_2") (pintype "passive"))
      (node (ref "USB1") (pin "1") (pinfunction "SH1_1") (pintype "passive"))
      (node (ref "USB1") (pin "2") (pinfunction "SH2_2") (pintype "passive"))
      (node (ref "USB1") (pin "3") (pinfunction "SH3_3") (pintype "passive"))
      (node (ref "USB1") (pin "4") (pinfunction "SH4_4") (pintype "passive"))
      (node (ref "USB1") (pin "A1") (pinfunction "GND_A1") (pintype "passive"))
      (node (ref "USB1") (pin "A12") (pinfunction "GND_A12") (pintype "passive"))
      (node (ref "USB1") (pin "B1") (pinfunction "GND_B1") (pintype "passive"))
      (node (ref "USB1") (pin "B12") (pinfunction "GND_B12") (pintype "passive"))
      (node (ref "Y1") (pin "2") (pinfunction "2_2") (pintype "passive"))
    )
    (net (code "45") (name "Net-(A2-Pad1)") (class "Default")
      (node (ref "A2") (pin "1") (pinfunction "1_1") (pintype "passive"))
      (node (ref "C11") (pin "1") (pinfunction "1_1") (pintype "passive"))
      (node (ref "C9") (pin "1") (pinfunction "1_1") (pintype "passive"))
      (node (ref "L3") (pin "2") (pinfunction "2_2") (pintype "passive"))
    )
    (net (code "46") (name "Net-(D1-A)") (class "Default")
      (node (ref "D1") (pin "1") (pinfunction "A_1") (pintype "passive"))
      (node (ref "R6") (pin "1") (pinfunction "1_1") (pintype "passive"))
      (node (ref "R7") (pin "2") (pinfunction "2_2") (pintype "passive"))
      (node (ref "U7") (pin "7") (pinfunction "RFIN_7") (pintype "passive"))
    )
    (net (code "47") (name "Net-(D2-K)") (class "Default")
      (node (ref "D2") (pin "2") (pinfunction "K_2") (pintype "passive"))
      (node (ref "D3") (pin "1") (pinfunction "A_1") (pintype "passive"))
    )
    (net (code "48") (name "Net-(D3-K)") (class "Default")
      (node (ref "D3") (pin "2") (pinfunction "K_2") (pintype "passive"))
      (node (ref "D4") (pin "1") (pinfunction "A_1") (pintype "passive"))
    )
    (net (code "49") (name "Net-(D4-K)") (class "Default")
      (node (ref "D4") (pin "2") (pinfunction "K_2") (pintype "passive"))
      (node (ref "D5") (pin "1") (pinfunction "A_1") (pintype "passive"))
    )
    (net (code "50") (name "Net-(D5-K)") (class "Default")
      (node (ref "D5") (pin "2") (pinfunction "K_2") (pintype "passive"))
      (node (ref "D6") (pin "1") (pinfunction "A_1") (pintype "passive"))
    )
    (net (code "51") (name "Net-(D6-K)") (class "Default")
      (node (ref "D6") (pin "2") (pinfunction "K_2") (pintype "passive"))
      (node (ref "D7") (pin "1") (pinfunction "A_1") (pintype "passive"))
    )
    (net (code "52") (name "Net-(D7-K)") (class "Default")
      (node (ref "D7") (pin "2") (pinfunction "K_2") (pintype "passive"))
      (node (ref "D8") (pin "1") (pinfunction "A_1") (pintype "passive"))
    )
    (net (code "53") (name "Net-(D8-K)") (class "Default")
      (node (ref "D8") (pin "2") (pinfunction "K_2") (pintype "passive"))
      (node (ref "D9") (pin "1") (pinfunction "A_1") (pintype "passive"))
    )
    (net (code "54") (name "Net-(D10-A)") (class "Default")
      (node (ref "D10") (pin "1") (pinfunction "A_1") (pintype "passive"))
      (node (ref "D9") (pin "2") (pinfunction "K_2") (pintype "passive"))
    )
    (net (code "55") (name "Net-(D10-K)") (class "Default")
      (node (ref "D10") (pin "2") (pinfunction "K_2") (pintype "passive"))
      (node (ref "D11") (pin "1") (pinfunction "A_1") (pintype "passive"))
    )
    (net (code "56") (name "Net-(D11-K)") (class "Default")
      (node (ref "D11") (pin "2") (pinfunction "K_2") (pintype "passive"))
      (node (ref "D12") (pin "1") (pinfunction "A_1") (pintype "passive"))
    )
    (net (code "57") (name "Net-(D12-K)") (class "Default")
      (node (ref "D12") (pin "2") (pinfunction "K_2") (pintype "passive"))
      (node (ref "D13") (pin "1") (pinfunction "A_1") (pintype "passive"))
    )
    (net (code "58") (name "Net-(D13-K)") (class "Default")
      (node (ref "D13") (pin "2") (pinfunction "K_2") (pintype "passive"))
      (node (ref "D14") (pin "1") (pinfunction "A_1") (pintype "passive"))
    )
    (net (code "59") (name "Net-(D14-K)") (class "Default")
      (node (ref "D14") (pin "2") (pinfunction "K_2") (pintype "passive"))
      (node (ref "D15") (pin "1") (pinfunction "A_1") (pintype "passive"))
    )
    (net (code "60") (name "Net-(D15-K)") (class "Default")
      (node (ref "D15") (pin "2") (pinfunction "K_2") (pintype "passive"))
      (node (ref "D16") (pin "1") (pinfunction "A_1") (pintype "passive"))
    )
    (net (code "61") (name "Net-(D16-K)") (class "Default")
      (node (ref "D16") (pin "2") (pinfunction "K_2") (pintype "passive"))
      (node (ref "D17") (pin "1") (pinfunction "A_1") (pintype "passive"))
    )
    (net (code "62") (name "Net-(D17-K)") (class "Default")
      (node (ref "D17") (pin "2") (pinfunction "K_2") (pintype "passive"))
      (node (ref "D18") (pin "1") (pinfunction "A_1") (pintype "passive"))
    )
    (net (code "63") (name "Net-(D18-K)") (class "Default")
      (node (ref "D18") (pin "2") (pinfunction "K_2") (pintype "passive"))
      (node (ref "D19") (pin "1") (pinfunction "A_1") (pintype "passive"))
    )
    (net (code "64") (name "Net-(D19-K)") (class "Default")
      (node (ref "D19") (pin "2") (pinfunction "K_2") (pintype "passive"))
      (node (ref "D20") (pin "1") (pinfunction "A_1") (pintype "passive"))
    )
    (net (code "65") (name "Net-(D20-K)") (class "Default")
      (node (ref "D20") (pin "2") (pinfunction "K_2") (pintype "passive"))
      (node (ref "D21") (pin "1") (pinfunction "A_1") (pintype "passive"))
    )
    (net (code "66") (name "Net-(D21-K)") (class "Default")
      (node (ref "D21") (pin "2") (pinfunction "K_2") (pintype "passive"))
      (node (ref "D22") (pin "1") (pinfunction "A_1") (pintype "passive"))
    )
    (net (code "67") (name "Net-(D22-K)") (class "Default")
      (node (ref "D22") (pin "2") (pinfunction "K_2") (pintype "passive"))
      (node (ref "D23") (pin "1") (pinfunction "A_1") (pintype "passive"))
    )
    (net (code "68") (name "Net-(D23-K)") (class "Default")
      (node (ref "D23") (pin "2") (pinfunction "K_2") (pintype "passive"))
      (node (ref "D24") (pin "1") (pinfunction "A_1") (pintype "passive"))
    )
    (net (code "69") (name "Net-(D24-K)") (class "Default")
      (node (ref "D24") (pin "2") (pinfunction "K_2") (pintype "passive"))
      (node (ref "D25") (pin "1") (pinfunction "A_1") (pintype "passive"))
    )
    (net (code "70") (name "Net-(D25-K)") (class "Default")
      (node (ref "D25") (pin "2") (pinfunction "K_2") (pintype "passive"))
      (node (ref "D26") (pin "1") (pinfunction "A_1") (pintype "passive"))
    )
    (net (code "71") (name "Net-(D26-K)") (class "Default")
      (node (ref "D26") (pin "2") (pinfunction "K_2") (pintype "passive"))
      (node (ref "D27") (pin "1") (pinfunction "A_1") (pintype "passive"))
    )
    (net (code "72") (name "Net-(D27-K)") (class "Default")
      (node (ref "D27") (pin "2") (pinfunction "K_2") (pintype "passive"))
      (node (ref "D28") (pin "1") (pinfunction "A_1") (pintype "passive"))
    )
    (net (code "73") (name "Net-(D28-K)") (class "Default")
      (node (ref "D28") (pin "2") (pinfunction "K_2") (pintype "passive"))
      (node (ref "D29") (pin "1") (pinfunction "A_1") (pintype "passive"))
    )
    (net (code "74") (name "Net-(D29-K)") (class "Default")
      (node (ref "D29") (pin "2") (pinfunction "K_2") (pintype "passive"))
      (node (ref "D30") (pin "1") (pinfunction "A_1") (pintype "passive"))
    )
    (net (code "75") (name "Net-(D30-K)") (class "Default")
      (node (ref "D30") (pin "2") (pinfunction "K_2") (pintype "passive"))
      (node (ref "D31") (pin "1") (pinfunction "A_1") (pintype "passive"))
    )
    (net (code "76") (name "Net-(D31-K)") (class "Default")
      (node (ref "D31") (pin "2") (pinfunction "K_2") (pintype "passive"))
      (node (ref "D32") (pin "1") (pinfunction "A_1") (pintype "passive"))
    )
    (net (code "77") (name "Net-(D32-K)") (class "Default")
      (node (ref "D32") (pin "2") (pinfunction "K_2") (pintype "passive"))
      (node (ref "D33") (pin "1") (pinfunction "A_1") (pintype "passive"))
    )
    (net (code "78") (name "Net-(D33-K)") (class "Default")
      (node (ref "D33") (pin "2") (pinfunction "K_2") (pintype "passive"))
      (node (ref "D34") (pin "1") (pinfunction "A_1") (pintype "passive"))
    )
    (net (code "79") (name "Net-(D34-K)") (class "Default")
      (node (ref "D34") (pin "2") (pinfunction "K_2") (pintype "passive"))
      (node (ref "D35") (pin "1") (pinfunction "A_1") (pintype "passive"))
    )
    (net (code "80") (name "Net-(D35-K)") (class "Default")
      (node (ref "D35") (pin "2") (pinfunction "K_2") (pintype "passive"))
      (node (ref "D36") (pin "1") (pinfunction "A_1") (pintype "passive"))
    )
    (net (code "81") (name "Net-(D36-K)") (class "Default")
      (node (ref "D36") (pin "2") (pinfunction "K_2") (pintype "passive"))
      (node (ref "D37") (pin "1") (pinfunction "A_1") (pintype "passive"))
    )
    (net (code "82") (name "Net-(L2-Pad1)") (class "Default")
      (node (ref "L2") (pin "1") (pinfunction "1_1") (pintype "passive"))
      (node (ref "U3") (pin "5") (pinfunction "IC-GND_5") (pintype "passive"))
      (node (ref "U3") (pin "6") (pinfunction "IC-GND_6") (pintype "passive"))
    )
    (net (code "83") (name "Net-(P1-Pad1)") (class "Default")
      (node (ref "P1") (pin "1") (pinfunction "1_1") (pintype "passive"))
      (node (ref "U1") (pin "4") (pinfunction "AC_4") (pintype "passive"))
    )
    (net (code "84") (name "Net-(P1-Pad2)") (class "Default")
      (node (ref "P1") (pin "2") (pinfunction "2_2") (pintype "passive"))
      (node (ref "U1") (pin "3") (pinfunction "AC_3") (pintype "passive"))
    )
    (net (code "85") (name "Net-(Q1-B)") (class "Default")
      (node (ref "Q1") (pin "1") (pinfunction "B_1") (pintype "passive"))
      (node (ref "R3") (pin "2") (pinfunction "2_2") (pintype "passive"))
    )
    (net (code "86") (name "Net-(Q2-B)") (class "Default")
      (node (ref "Q2") (pin "1") (pinfunction "B_1") (pintype "passive"))
      (node (ref "R4") (pin "2") (pinfunction "2_2") (pintype "passive"))
    )
    (net (code "87") (name "Net-(R7-Pad1)") (class "Default")
      (node (ref "R7") (pin "1") (pinfunction "1_1") (pintype "passive"))
      (node (ref "S1") (pin "2") (pinfunction "2_2") (pintype "passive"))
    )
    (net (code "88") (name "Net-(U2-*RST)") (class "Default")
      (node (ref "R1") (pin "2") (pinfunction "2_2") (pintype "passive"))
      (node (ref "U2") (pin "9") (pinfunction "*RST_9") (pintype "passive"))
    )
    (net (code "89") (name "Net-(U2-TXD)") (class "Default")
      (node (ref "R2") (pin "2") (pinfunction "2_2") (pintype "passive"))
      (node (ref "U2") (pin "26") (pinfunction "TXD_26") (pintype "passive"))
    )
    (net (code "90") (name "Net-(U3-DRAIN)") (class "Default")
      (node (ref "C4") (pin "1") (pinfunction "1_1") (pintype "passive"))
      (node (ref "L1") (pin "2") (pinfunction "2_2") (pintype "passive"))
      (node (ref "U3") (pin "4") (pinfunction "DRAIN_4") (pintype "passive"))
    )
    (net (code "91") (name "Net-(U4-BYPASS)") (class "Default")
      (node (ref "C7") (pin "2") (pinfunction "2_2") (pintype "passive"))
      (node (ref "U4") (pin "4") (pinfunction "BYPASS_4") (pintype "passive"))
    )
    (net (code "92") (name "Net-(U5-CAGC)") (class "Default")
      (node (ref "C10") (pin "2") (pinfunction "2_2") (pintype "passive"))
      (node (ref "U5") (pin "7") (pinfunction "CAGC_7") (pintype "passive"))
    )
    (net (code "93") (name "Net-(U5-CTH)") (class "Default")
      (node (ref "C12") (pin "2") (pinfunction "2_2") (pintype "passive"))
      (node (ref "U5") (pin "6") (pinfunction "CTH_6") (pintype "passive"))
    )
    (net (code "94") (name "Net-(U5-RFIN)") (class "Default")
      (node (ref "C9") (pin "2") (pinfunction "2_2") (pintype "passive"))
      (node (ref "L4") (pin "2") (pinfunction "2_2") (pintype "passive"))
      (node (ref "U5") (pin "1") (pinfunction "RFIN_1") (pintype "passive"))
    )
    (net (code "95") (name "Net-(U5-SHUT)") (class "Default")
      (node (ref "U5") (pin "4") (pinfunction "SHUT_4") (pintype "passive"))
      (node (ref "U7") (pin "2") (pinfunction "I0_2") (pintype "passive"))
    )
    (net (code "96") (name "Net-(U5-XOSC)") (class "Default")
      (node (ref "U5") (pin "8") (pinfunction "XOSC_8") (pintype "passive"))
      (node (ref "Y1") (pin "1") (pinfunction "1_1") (pintype "passive"))
    )
    (net (code "97") (name "Net-(U6-LNA_IN)") (class "Default")
      (node (ref "A1") (pin "1") (pinfunction "1_1") (pintype "passive"))
      (node (ref "U6") (pin "2") (pinfunction "LNA_IN_2") (pintype "passive"))
    )
    (net (code "98") (name "Net-(U8-CS)") (class "Default")
      (node (ref "R9") (pin "2") (pinfunction "2_2") (pintype "passive"))
      (node (ref "U8") (pin "8") (pinfunction "CS_8") (pintype "passive"))
    )
    (net (code "99") (name "Net-(U8-DRAIN)") (class "Default")
      (node (ref "L5") (pin "1") (pinfunction "1_1") (pintype "passive"))
      (node (ref "U8") (pin "5") (pinfunction "DRAIN_5") (pintype "passive"))
    )
    (net (code "100") (name "Net-(U8-ROVP)") (class "Default")
      (node (ref "R8") (pin "2") (pinfunction "2_2") (pintype "passive"))
      (node (ref "U8") (pin "1") (pinfunction "ROVP_1") (pintype "passive"))
    )
    (net (code "101") (name "VDD_5V") (class "Default")
      (node (ref "C16") (pin "1") (pinfunction "1_1") (pintype "passive"))
      (node (ref "C5") (pin "1") (pinfunction "1_1") (pintype "passive"))
      (node (ref "L2") (pin "2") (pinfunction "2_2") (pintype "passive"))
      (node (ref "R1") (pin "1") (pinfunction "1_1") (pintype "passive"))
      (node (ref "U2") (pin "7") (pinfunction "REGIN_7") (pintype "passive"))
      (node (ref "U2") (pin "8") (pinfunction "VBUS_8") (pintype "passive"))
      (node (ref "U3") (pin "1") (pinfunction "VOUT_1") (pintype "passive"))
      (node (ref "U4") (pin "1") (pinfunction "VIN_1") (pintype "passive"))
      (node (ref "U4") (pin "3") (pinfunction "ON/OFF_3") (pintype "passive"))
      (node (ref "USB1") (pin "A4") (pinfunction "VBUS_A4") (pintype "passive"))
      (node (ref "USB1") (pin "A9") (pinfunction "VBUS_A9") (pintype "passive"))
      (node (ref "USB1") (pin "B4") (pinfunction "VBUS_B4") (pintype "passive"))
      (node (ref "USB1") (pin "B9") (pinfunction "VBUS_B9") (pintype "passive"))
    )
    (net (code "102") (name "unconnected-(U2-*SUSPEND-Pad11)") (class "Default")
      (node (ref "U2") (pin "11") (pinfunction "*SUSPEND_11") (pintype "passive"))
    )
    (net (code "103") (name "unconnected-(U2-CTS-Pad23)") (class "Default")
      (node (ref "U2") (pin "23") (pinfunction "CTS_23") (pintype "passive"))
    )
    (net (code "104") (name "unconnected-(U2-DCD-Pad1)") (class "Default")
      (node (ref "U2") (pin "1") (pinfunction "DCD_1") (pintype "passive"))
    )
    (net (code "105") (name "unconnected-(U2-DSR-Pad27)") (class "Default")
      (node (ref "U2") (pin "27") (pinfunction "DSR_27") (pintype "passive"))
    )
    (net (code "106") (name "unconnected-(U2-NC-Pad10)") (class "Default")
      (node (ref "U2") (pin "10") (pinfunction "NC_10") (pintype "passive"))
    )
    (net (code "107") (name "unconnected-(U2-NC-Pad13)") (class "Default")
      (node (ref "U2") (pin "13") (pinfunction "NC_13") (pintype "passive"))
    )
    (net (code "108") (name "unconnected-(U2-NC-Pad14)") (class "Default")
      (node (ref "U2") (pin "14") (pinfunction "NC_14") (pintype "passive"))
    )
    (net (code "109") (name "unconnected-(U2-NC-Pad15)") (class "Default")
      (node (ref "U2") (pin "15") (pinfunction "NC_15") (pintype "passive"))
    )
    (net (code "110") (name "unconnected-(U2-NC-Pad16)") (class "Default")
      (node (ref "U2") (pin "16") (pinfunction "NC_16") (pintype "passive"))
    )
    (net (code "111") (name "unconnected-(U2-NC-Pad17)") (class "Default")
      (node (ref "U2") (pin "17") (pinfunction "NC_17") (pintype "passive"))
    )
    (net (code "112") (name "unconnected-(U2-NC-Pad18)") (class "Default")
      (node (ref "U2") (pin "18") (pinfunction "NC_18") (pintype "passive"))
    )
    (net (code "113") (name "unconnected-(U2-NC-Pad19)") (class "Default")
      (node (ref "U2") (pin "19") (pinfunction "NC_19") (pintype "passive"))
    )
    (net (code "114") (name "unconnected-(U2-NC-Pad20)") (class "Default")
      (node (ref "U2") (pin "20") (pinfunction "NC_20") (pintype "passive"))
    )
    (net (code "115") (name "unconnected-(U2-NC-Pad21)") (class "Default")
      (node (ref "U2") (pin "21") (pinfunction "NC_21") (pintype "passive"))
    )
    (net (code "116") (name "unconnected-(U2-NC-Pad22)") (class "Default")
      (node (ref "U2") (pin "22") (pinfunction "NC_22") (pintype "passive"))
    )
    (net (code "117") (name "unconnected-(U2-RI-Pad2)") (class "Default")
      (node (ref "U2") (pin "2") (pinfunction "RI_2") (pintype "passive"))
    )
    (net (code "118") (name "unconnected-(U2-SUSPEND-Pad12)") (class "Default")
      (node (ref "U2") (pin "12") (pinfunction "SUSPEND_12") (pintype "passive"))
    )
    (net (code "119") (name "unconnected-(U2-VDD-Pad6)") (class "Default")
      (node (ref "U2") (pin "6") (pinfunction "VDD_6") (pintype "passive"))
    )
    (net (code "120") (name "unconnected-(U3-FB-Pad8)") (class "Default")
      (node (ref "U3") (pin "8") (pinfunction "FB_8") (pintype "passive"))
    )
    (net (code "121") (name "unconnected-(U3-NC-Pad3)") (class "Default")
      (node (ref "U3") (pin "3") (pinfunction "NC_3") (pintype "passive"))
    )
    (net (code "122") (name "unconnected-(U6-CAP1_NC-Pad48)") (class "Default")
      (node (ref "U6") (pin "48") (pinfunction "CAP1_NC_48") (pintype "passive"))
    )
    (net (code "123") (name "unconnected-(U6-CAP2_NC-Pad47)") (class "Default")
      (node (ref "U6") (pin "47") (pinfunction "CAP2_NC_47") (pintype "passive"))
    )
    (net (code "124") (name "unconnected-(U6-VDD_SDIO_NC-Pad26)") (class "Default")
      (node (ref "U6") (pin "26") (pinfunction "VDD_SDIO_NC_26") (pintype "passive"))
    )
    (net (code "125") (name "unconnected-(U6-XTAL_N_NC-Pad44)") (class "Default")
      (node (ref "U6") (pin "44") (pinfunction "XTAL_N_NC_44") (pintype "passive"))
    )
    (net (code "126") (name "unconnected-(U6-XTAL_P_NC-Pad45)") (class "Default")
      (node (ref "U6") (pin "45") (pinfunction "XTAL_P_NC_45") (pintype "passive"))
    )
    (net (code "127") (name "unconnected-(U7-GND-Pad8)") (class "Default")
      (node (ref "U7") (pin "8") (pinfunction "GND_8") (pintype "passive"))
    )
    (net (code "128") (name "unconnected-(U8-NC-Pad3)") (class "Default")
      (node (ref "U8") (pin "3") (pinfunction "NC_3") (pintype "passive"))
    )
    (net (code "129") (name "unconnected-(U8-NC-Pad6)") (class "Default")
      (node (ref "U8") (pin "6") (pinfunction "NC_6") (pintype "passive"))
    )
    (net (code "130") (name "unconnected-(USB1-CC1-PadA5)") (class "Default")
      (node (ref "USB1") (pin "A5") (pinfunction "CC1_A5") (pintype "passive"))
    )
    (net (code "131") (name "unconnected-(USB1-CC2-PadB5)") (class "Default")
      (node (ref "USB1") (pin "B5") (pinfunction "CC2_B5") (pintype "passive"))
    )
    (net (code "132") (name "unconnected-(USB1-RX1+-PadB11)") (class "Default")
      (node (ref "USB1") (pin "B11") (pinfunction "RX1+_B11") (pintype "passive"))
    )
    (net (code "133") (name "unconnected-(USB1-RX1--PadB10)") (class "Default")
      (node (ref "USB1") (pin "B10") (pinfunction "RX1-_B10") (pintype "passive"))
    )
    (net (code "134") (name "unconnected-(USB1-RX2+-PadA11)") (class "Default")
      (node (ref "USB1") (pin "A11") (pinfunction "RX2+_A11") (pintype "passive"))
    )
    (net (code "135") (name "unconnected-(USB1-RX2--PadA10)") (class "Default")
      (node (ref "USB1") (pin "A10") (pinfunction "RX2-_A10") (pintype "passive"))
    )
    (net (code "136") (name "unconnected-(USB1-SBU1-PadA8)") (class "Default")
      (node (ref "USB1") (pin "A8") (pinfunction "SBU1_A8") (pintype "passive"))
    )
    (net (code "137") (name "unconnected-(USB1-SBU2-PadB8)") (class "Default")
      (node (ref "USB1") (pin "B8") (pinfunction "SBU2_B8") (pintype "passive"))
    )
    (net (code "138") (name "unconnected-(USB1-TX1+-PadA2)") (class "Default")
      (node (ref "USB1") (pin "A2") (pinfunction "TX1+_A2") (pintype "passive"))
    )
    (net (code "139") (name "unconnected-(USB1-TX1--PadA3)") (class "Default")
      (node (ref "USB1") (pin "A3") (pinfunction "TX1-_A3") (pintype "passive"))
    )
    (net (code "140") (name "unconnected-(USB1-TX2+-PadB2)") (class "Default")
      (node (ref "USB1") (pin "B2") (pinfunction "TX2+_B2") (pintype "passive"))
    )
    (net (code "141") (name "unconnected-(USB1-TX2--PadB3)") (class "Default")
      (node (ref "USB1") (pin "B3") (pinfunction "TX2-_B3") (pintype "passive"))
    )
  )
)
